# THYRISTOR_POWER_REGULATOR.net
KiCad netlist of a schematic drawn in Altium Designer
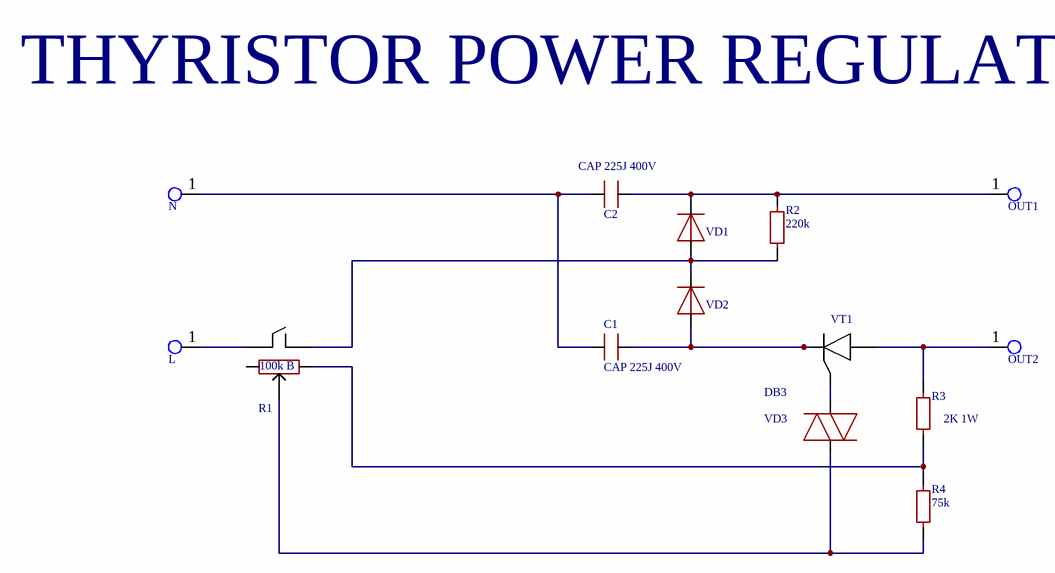
[diagram p0: THYRISTOR POWER REGULATOR.SchDoc]

(export (version "E")
  (design (tool "Eeschema 10.0.6"))
  (components
    (comp (ref "C1")
      (value "CAP 225J 400V")
      (footprint "CAP 225J 400V")
      (libsource (lib "CAP 225J 400V") (part "CAP 225J 400V"))
    )
    (comp (ref "C2")
      (value "CAP 225J 400V")
      (footprint "CAP 225J 400V")
      (libsource (lib "CAP 225J 400V") (part "CAP 225J 400V"))
    )
    (comp (ref "L")
      (value "Test_Point_PCB")
      (footprint "Test_Point")
      (description "Test_Point")
      (libsource (lib "TEST_POINT") (part "TP_PCB?"))
    )
    (comp (ref "N")
      (value "Test_Point_PCB")
      (footprint "Test_Point")
      (description "Test_Point")
      (libsource (lib "") (part "TP_PCB?_1"))
    )
    (comp (ref "OUT1")
      (value "Test_Point_PCB")
      (footprint "Test_Point")
      (description "Test_Point")
      (libsource (lib "TEST_POINT") (part "TP_PCB?"))
    )
    (comp (ref "OUT2")
      (value "Test_Point_PCB")
      (footprint "Test_Point")
      (description "Test_Point")
      (libsource (lib "TEST_POINT") (part "TP_PCB?"))
    )
    (comp (ref "R1") (value "100k B") (footprint "RES_VAR") (libsource (lib "RES_VAR") (part "RES_VAR")))
    (comp (ref "R2")
      (value "220k")
      (footprint "RES-1206")
      (libsource (lib "PASSIVE_COMPONENTS") (part "RES-CONST"))
    )
    (comp (ref "R3")
      (value "2K 1W")
      (footprint "RES-2512")
      (libsource (lib "PASSIVE_COMPONENTS") (part "RES-CONST"))
    )
    (comp (ref "R4")
      (value "75k")
      (footprint "RES-1206")
      (libsource (lib "PASSIVE_COMPONENTS") (part "RES-CONST"))
    )
    (comp (ref "VD1")
      (value "DIODE")
      (footprint "DO-214AA")
      (description "Diode Schottky 40 V 3A Surface Mount SMB")
      (fields (field (name "PART NUMBER") "B340B-13-F") (field (name "MANUFACTURER") "Diodes Incorporated"))
      (libsource (lib "Database_Libs2") (part "DIODE"))
    )
    (comp (ref "VD2")
      (value "DIODE")
      (footprint "DO-214AA")
      (description "Diode Schottky 40 V 3A Surface Mount SMB")
      (fields (field (name "PART NUMBER") "B340B-13-F") (field (name "MANUFACTURER") "Diodes Incorporated"))
      (libsource (lib "Database_Libs2") (part "DIODE"))
    )
    (comp (ref "VD3") (value "DB3") (footprint "DB3") (libsource (lib "DB3") (part "DIODE")))
    (comp (ref "VT1") (value "TYN412") (footprint "TO-220-3") (libsource (lib "TYN412") (part "TYN412")))
  )
  (nets
    (net (code "1") (name "Net-(C1-A)") (class "Default")
      (node (ref "C1") (pin "2") (pinfunction "A_2") (pintype "passive"))
      (node (ref "C2") (pin "2") (pinfunction "A_2") (pintype "passive"))
      (node (ref "N") (pin "1") (pinfunction "G9_1") (pintype "passive"))
    )
    (net (code "2") (name "Net-(C1-C)") (class "Default")
      (node (ref "C1") (pin "1") (pinfunction "C_1") (pintype "passive"))
      (node (ref "VD2") (pin "2") (pinfunction "A_2") (pintype "passive"))
      (node (ref "VT1") (pin "1") (pintype "passive"))
    )
    (net (code "3") (name "Net-(C2-C)") (class "Default")
      (node (ref "C2") (pin "1") (pinfunction "C_1") (pintype "passive"))
      (node (ref "OUT1") (pin "1") (pinfunction "G9_1") (pintype "passive"))
      (node (ref "R2") (pin "1") (pinfunction "1_1") (pintype "passive"))
      (node (ref "VD1") (pin "1") (pinfunction "C_1") (pintype "passive"))
    )
    (net (code "4") (name "Net-(L-G9)") (class "Default")
      (node (ref "L") (pin "1") (pinfunction "G9_1") (pintype "passive"))
      (node (ref "R1") (pin "5") (pintype "passive"))
    )
    (net (code "5") (name "Net-(OUT2-G9)") (class "Default")
      (node (ref "OUT2") (pin "1") (pinfunction "G9_1") (pintype "passive"))
      (node (ref "R3") (pin "2") (pinfunction "2_2") (pintype "passive"))
      (node (ref "VT1") (pin "2") (pintype "passive"))
    )
    (net (code "6") (name "Net-(R1-Pad1)") (class "Default")
      (node (ref "R1") (pin "1") (pintype "passive"))
      (node (ref "R3") (pin "1") (pinfunction "1_1") (pintype "passive"))
      (node (ref "R4") (pin "1") (pinfunction "1_1") (pintype "passive"))
    )
    (net (code "7") (name "Net-(VD1-A)") (class "Default")
      (node (ref "R1") (pin "4") (pintype "passive"))
      (node (ref "R2") (pin "2") (pinfunction "2_2") (pintype "passive"))
      (node (ref "VD1") (pin "2") (pinfunction "A_2") (pintype "passive"))
      (node (ref "VD2") (pin "1") (pinfunction "C_1") (pintype "passive"))
    )
    (net (code "8") (name "Net-(VD3-A)") (class "Default")
      (node (ref "R1") (pin "2") (pintype "passive"))
      (node (ref "R4") (pin "2") (pinfunction "2_2") (pintype "passive"))
      (node (ref "VD3") (pin "2") (pinfunction "A_2") (pintype "passive"))
    )
    (net (code "9") (name "Net-(VD3-C)") (class "Default")
      (node (ref "VD3") (pin "1") (pinfunction "C_1") (pintype "passive"))
      (node (ref "VT1") (pin "3") (pintype "passive"))
    )
    (net (code "10") (name "unconnected-(R1-Pad3)") (class "Default")
      (node (ref "R1") (pin "3") (pintype "passive"))
    )
  )
)
